# SCH___2021-12-05.net
KiCad netlist of a schematic drawn in EasyEDA
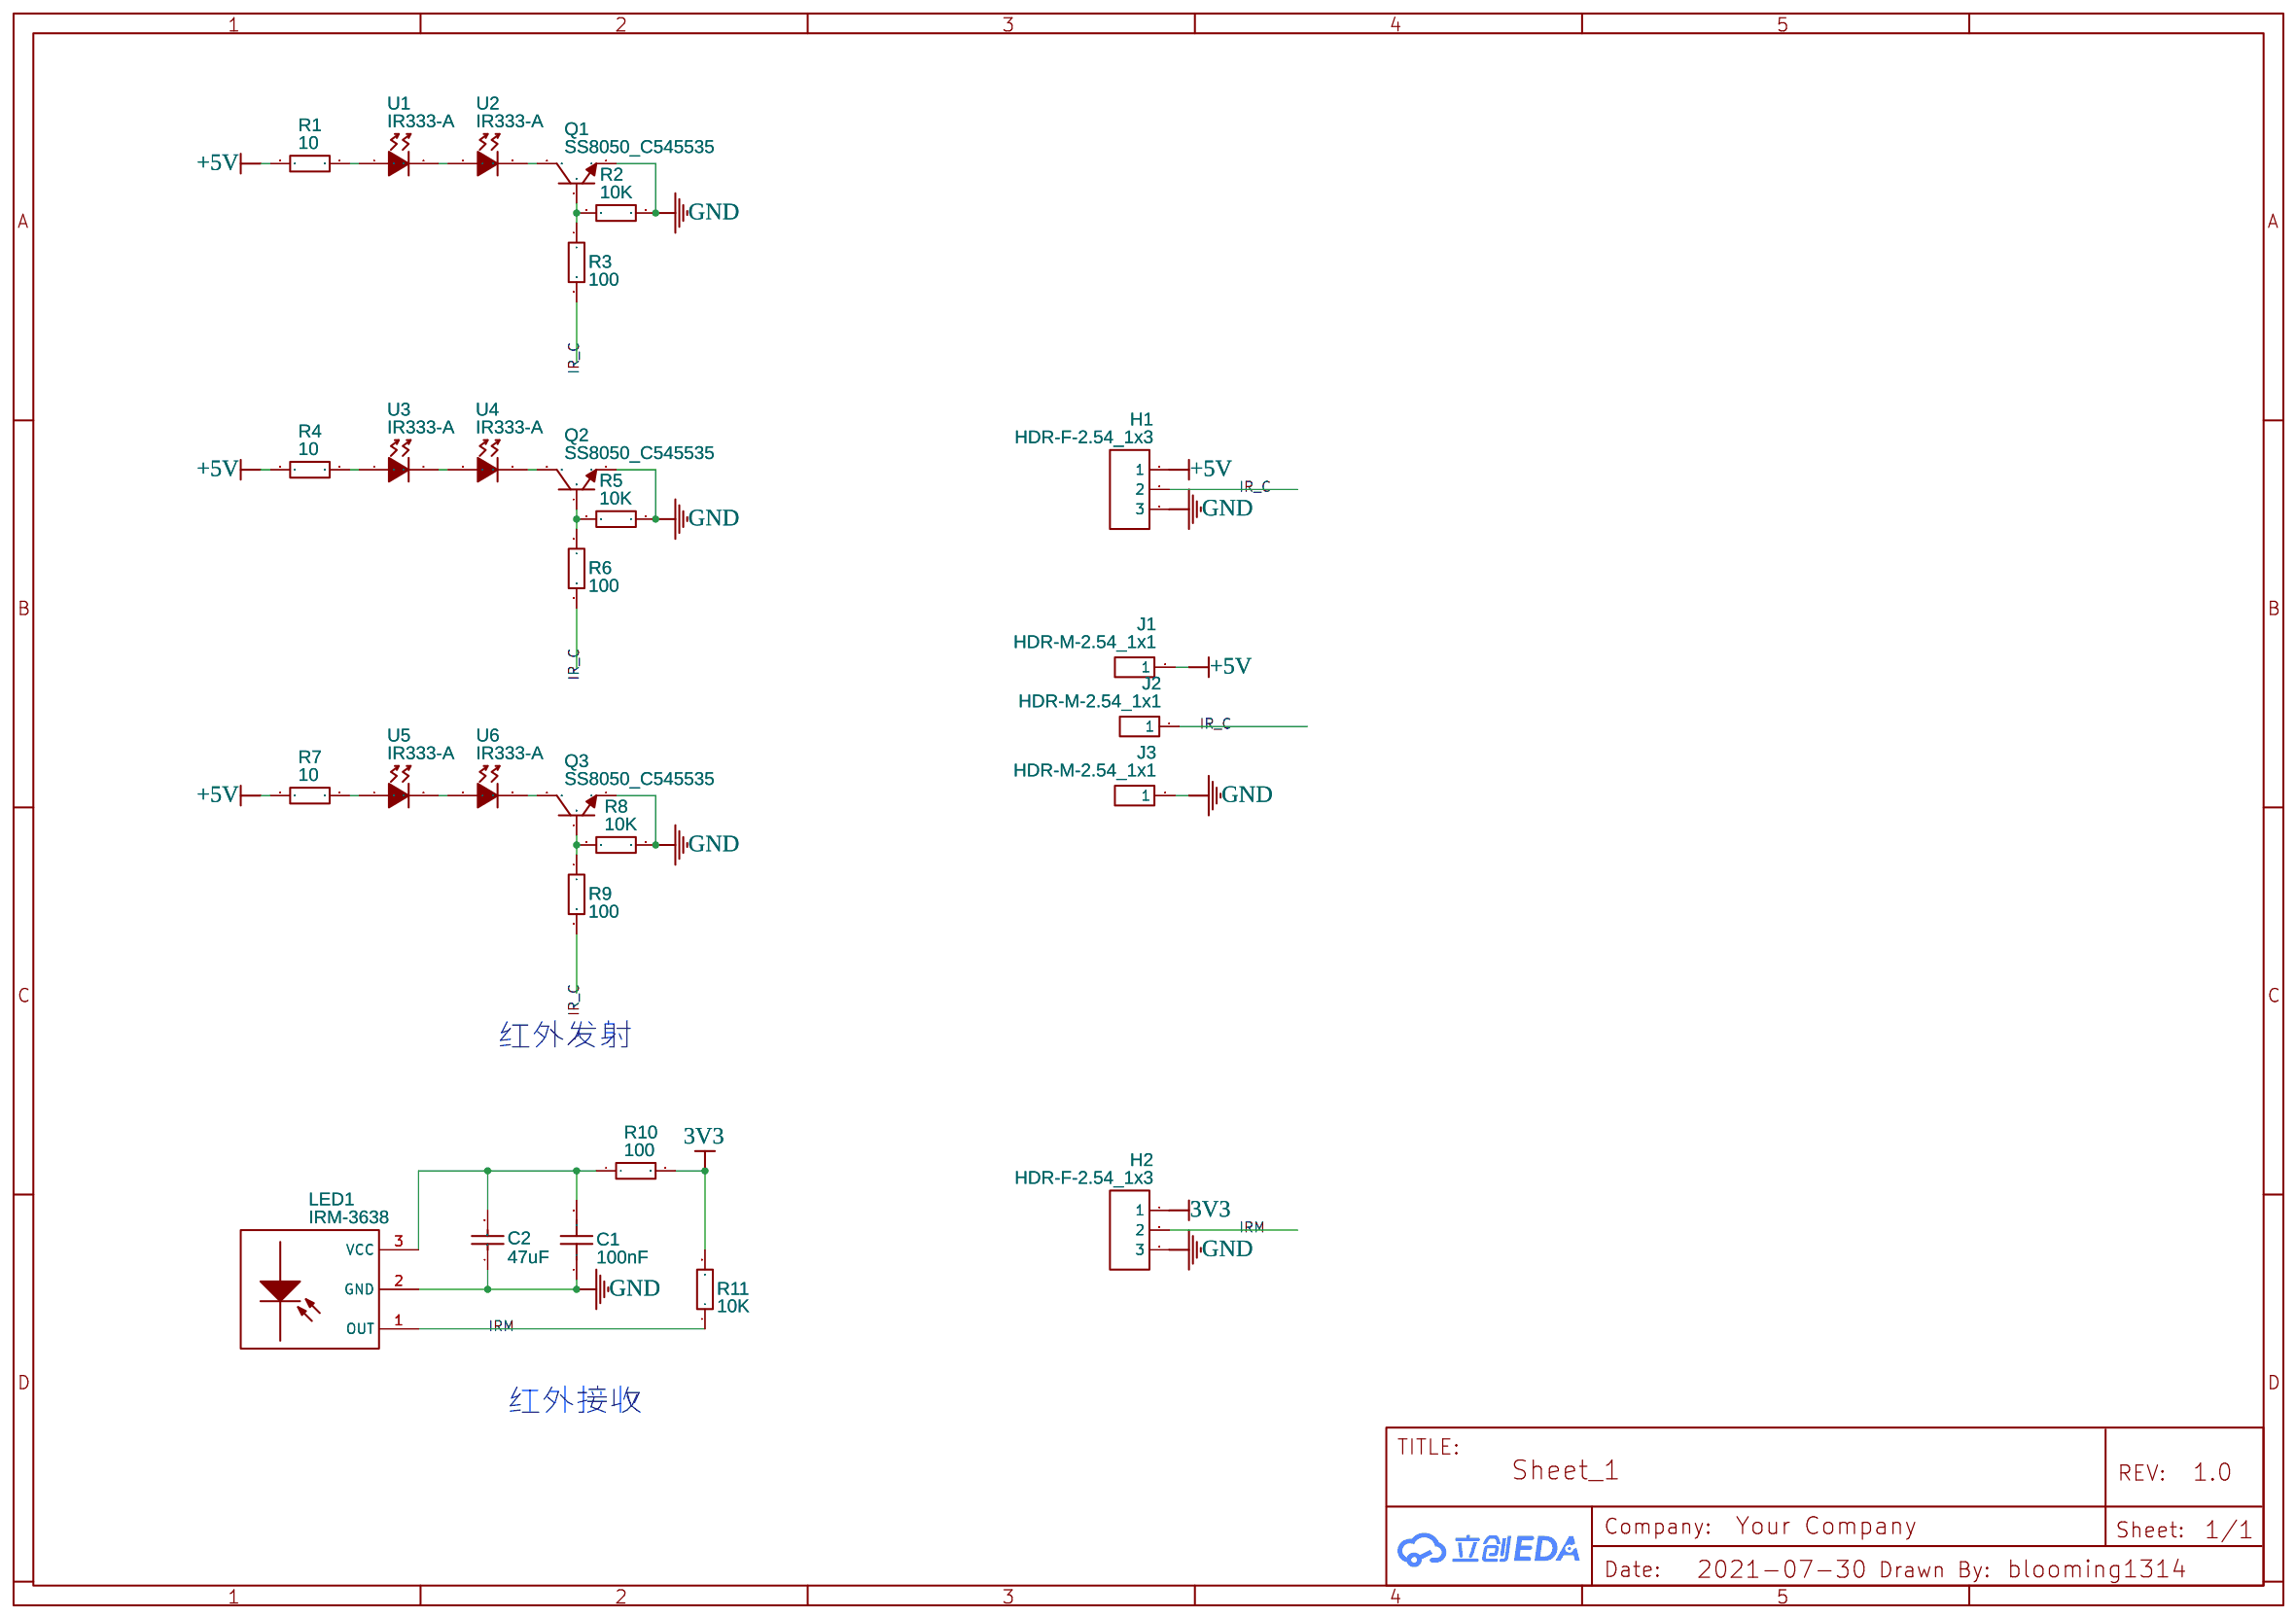
[diagram p0: schematic sheet]

(export (version "E")
  (design (tool "Eeschema 10.0.6"))
  (components
    (comp (ref "C1")
      (value "100nF")
      (fields
        (field (name "BOM_Manufacturer Part") "CC0603KRX7R7BB104")
        (field (name "BOM_Supplier Part") "C108079")
      )
      (libsource (lib "") (part "CC0603KRX7R7BB104"))
    )
    (comp (ref "C2")
      (value "47uF")
      (fields
        (field (name "BOM_Manufacturer Part") "GRM188R60J476ME15D")
        (field (name "BOM_Supplier Part") "C140782")
      )
      (libsource (lib "") (part "GRM188R60J476ME15D"))
    )
    (comp (ref "H1")
      (value "HDR-F-2.54_1x3")
      (fields (field (name "BOM_Supplier Part") "C146690"))
      (libsource (lib "") (part "HDR-F-2.54_1x3"))
    )
    (comp (ref "H2")
      (value "HDR-F-2.54_1x3")
      (fields (field (name "BOM_Supplier Part") "C146690"))
      (libsource (lib "") (part "HDR-F-2.54_1x3"))
    )
    (comp (ref "J1")
      (value "HDR-M-2.54_1x1")
      (fields (field (name "BOM_Supplier Part") "C81276"))
      (libsource (lib "") (part "HDR-M-2.54_1x1"))
    )
    (comp (ref "J2")
      (value "HDR-M-2.54_1x1")
      (fields (field (name "BOM_Supplier Part") "C81276"))
      (libsource (lib "") (part "HDR-M-2.54_1x1_1"))
    )
    (comp (ref "J3")
      (value "HDR-M-2.54_1x1")
      (fields (field (name "BOM_Supplier Part") "C81276"))
      (libsource (lib "") (part "HDR-M-2.54_1x1"))
    )
    (comp (ref "LED1")
      (value "IRM-3638")
      (fields (field (name "BOM_Supplier Part") "C131209"))
      (libsource (lib "") (part "IRM-3638"))
    )
    (comp (ref "Q1")
      (value "SS8050_C545535")
      (fields (field (name "BOM_Manufacturer Part") "SS8050") (field (name "BOM_Supplier Part") "C545535"))
      (libsource (lib "") (part "SS8050_C545535"))
    )
    (comp (ref "Q2")
      (value "SS8050_C545535")
      (fields (field (name "BOM_Manufacturer Part") "SS8050") (field (name "BOM_Supplier Part") "C545535"))
      (libsource (lib "") (part "SS8050_C545535"))
    )
    (comp (ref "Q3")
      (value "SS8050_C545535")
      (fields (field (name "BOM_Manufacturer Part") "SS8050") (field (name "BOM_Supplier Part") "C545535"))
      (libsource (lib "") (part "SS8050_C545535"))
    )
    (comp (ref "R1")
      (value "10")
      (fields
        (field (name "BOM_Manufacturer Part") "AECR0603F10R0K9")
        (field (name "BOM_Supplier Part") "C328336")
      )
      (libsource (lib "") (part "AECR0603F10R0K9"))
    )
    (comp (ref "R2")
      (value "10K")
      (fields
        (field (name "BOM_Manufacturer Part") "0603WAF1002T5E")
        (field (name "BOM_Supplier Part") "C25804")
      )
      (libsource (lib "") (part "0603WAF1002T5E"))
    )
    (comp (ref "R3")
      (value "100")
      (fields
        (field (name "BOM_Manufacturer Part") "0603WAJ0101T5E")
        (field (name "BOM_Supplier Part") "C25201")
      )
      (libsource (lib "") (part "0603WAJ0101T5E"))
    )
    (comp (ref "R4")
      (value "10")
      (fields
        (field (name "BOM_Manufacturer Part") "AECR0603F10R0K9")
        (field (name "BOM_Supplier Part") "C328336")
      )
      (libsource (lib "") (part "AECR0603F10R0K9"))
    )
    (comp (ref "R5")
      (value "10K")
      (fields
        (field (name "BOM_Manufacturer Part") "0603WAF1002T5E")
        (field (name "BOM_Supplier Part") "C25804")
      )
      (libsource (lib "") (part "0603WAF1002T5E"))
    )
    (comp (ref "R6")
      (value "100")
      (fields
        (field (name "BOM_Manufacturer Part") "0603WAJ0101T5E")
        (field (name "BOM_Supplier Part") "C25201")
      )
      (libsource (lib "") (part "0603WAJ0101T5E"))
    )
    (comp (ref "R7")
      (value "10")
      (fields
        (field (name "BOM_Manufacturer Part") "AECR0603F10R0K9")
        (field (name "BOM_Supplier Part") "C328336")
      )
      (libsource (lib "") (part "AECR0603F10R0K9"))
    )
    (comp (ref "R8")
      (value "10K")
      (fields
        (field (name "BOM_Manufacturer Part") "0603WAF1002T5E")
        (field (name "BOM_Supplier Part") "C25804")
      )
      (libsource (lib "") (part "0603WAF1002T5E"))
    )
    (comp (ref "R9")
      (value "100")
      (fields
        (field (name "BOM_Manufacturer Part") "0603WAJ0101T5E")
        (field (name "BOM_Supplier Part") "C25201")
      )
      (libsource (lib "") (part "0603WAJ0101T5E"))
    )
    (comp (ref "R10")
      (value "100")
      (fields
        (field (name "BOM_Manufacturer Part") "0603WAJ0101T5E")
        (field (name "BOM_Supplier Part") "C25201")
      )
      (libsource (lib "") (part "0603WAJ0101T5E_1"))
    )
    (comp (ref "R11")
      (value "10K")
      (fields
        (field (name "BOM_Manufacturer Part") "0603WAF1002T5E")
        (field (name "BOM_Supplier Part") "C25804")
      )
      (libsource (lib "") (part "0603WAF1002T5E_1"))
    )
    (comp (ref "U1")
      (value "IR333-A")
      (fields (field (name "BOM_Supplier Part") "C95407"))
      (libsource (lib "") (part "IR333-A"))
    )
    (comp (ref "U2")
      (value "IR333-A")
      (fields (field (name "BOM_Supplier Part") "C95407"))
      (libsource (lib "") (part "IR333-A"))
    )
    (comp (ref "U3")
      (value "IR333-A")
      (fields (field (name "BOM_Supplier Part") "C95407"))
      (libsource (lib "") (part "IR333-A"))
    )
    (comp (ref "U4")
      (value "IR333-A")
      (fields (field (name "BOM_Supplier Part") "C95407"))
      (libsource (lib "") (part "IR333-A"))
    )
    (comp (ref "U5")
      (value "IR333-A")
      (fields (field (name "BOM_Supplier Part") "C95407"))
      (libsource (lib "") (part "IR333-A"))
    )
    (comp (ref "U6")
      (value "IR333-A")
      (fields (field (name "BOM_Supplier Part") "C95407"))
      (libsource (lib "") (part "IR333-A"))
    )
  )
  (nets
    (net (code "1") (name "+5V") (class "Default")
      (node (ref "H1") (pin "1") (pinfunction "1_1") (pintype "input"))
      (node (ref "J1") (pin "1") (pinfunction "1_1") (pintype "input"))
      (node (ref "R1") (pin "2") (pinfunction "2_2") (pintype "unspecified"))
      (node (ref "R4") (pin "2") (pinfunction "2_2") (pintype "unspecified"))
      (node (ref "R7") (pin "2") (pinfunction "2_2") (pintype "unspecified"))
    )
    (net (code "2") (name "/IRM") (class "Default")
      (node (ref "H2") (pin "2") (pinfunction "2_2") (pintype "input"))
      (node (ref "LED1") (pin "1") (pinfunction "OUT_1") (pintype "input"))
      (node (ref "R11") (pin "1") (pinfunction "1_1") (pintype "input"))
    )
    (net (code "3") (name "/IR_C") (class "Default")
      (node (ref "H1") (pin "2") (pinfunction "2_2") (pintype "input"))
      (node (ref "J2") (pin "1") (pinfunction "1_1") (pintype "input"))
      (node (ref "R3") (pin "2") (pinfunction "2_2") (pintype "input"))
      (node (ref "R6") (pin "2") (pinfunction "2_2") (pintype "input"))
      (node (ref "R9") (pin "2") (pinfunction "2_2") (pintype "input"))
    )
    (net (code "4") (name "3V3") (class "Default")
      (node (ref "H2") (pin "1") (pinfunction "1_1") (pintype "input"))
      (node (ref "R10") (pin "2") (pinfunction "2_2") (pintype "input"))
      (node (ref "R11") (pin "2") (pinfunction "2_2") (pintype "input"))
    )
    (net (code "5") (name "GND") (class "Default")
      (node (ref "C1") (pin "1") (pinfunction "1_1") (pintype "unspecified"))
      (node (ref "C2") (pin "1") (pinfunction "1_1") (pintype "input"))
      (node (ref "H1") (pin "3") (pinfunction "3_3") (pintype "input"))
      (node (ref "H2") (pin "3") (pinfunction "3_3") (pintype "input"))
      (node (ref "J3") (pin "1") (pinfunction "1_1") (pintype "input"))
      (node (ref "LED1") (pin "2") (pinfunction "GND_2") (pintype "input"))
      (node (ref "Q1") (pin "2") (pinfunction "E_2") (pintype "input"))
      (node (ref "Q2") (pin "2") (pinfunction "E_2") (pintype "input"))
      (node (ref "Q3") (pin "2") (pinfunction "E_2") (pintype "input"))
      (node (ref "R2") (pin "1") (pinfunction "1_1") (pintype "input"))
      (node (ref "R5") (pin "1") (pinfunction "1_1") (pintype "input"))
      (node (ref "R8") (pin "1") (pinfunction "1_1") (pintype "input"))
    )
    (net (code "6") (name "Net-(LED1-VCC)") (class "Default")
      (node (ref "C1") (pin "2") (pinfunction "2_2") (pintype "unspecified"))
      (node (ref "C2") (pin "2") (pinfunction "2_2") (pintype "input"))
      (node (ref "LED1") (pin "3") (pinfunction "VCC_3") (pintype "input"))
      (node (ref "R10") (pin "1") (pinfunction "1_1") (pintype "input"))
    )
    (net (code "7") (name "Net-(Q1-B)") (class "Default")
      (node (ref "Q1") (pin "1") (pinfunction "B_1") (pintype "input"))
      (node (ref "R2") (pin "2") (pinfunction "2_2") (pintype "input"))
      (node (ref "R3") (pin "1") (pinfunction "1_1") (pintype "input"))
    )
    (net (code "8") (name "Net-(Q1-C)") (class "Default")
      (node (ref "Q1") (pin "3") (pinfunction "C_3") (pintype "input"))
      (node (ref "U2") (pin "2") (pinfunction "C_2") (pintype "input"))
    )
    (net (code "9") (name "Net-(Q2-B)") (class "Default")
      (node (ref "Q2") (pin "1") (pinfunction "B_1") (pintype "input"))
      (node (ref "R5") (pin "2") (pinfunction "2_2") (pintype "input"))
      (node (ref "R6") (pin "1") (pinfunction "1_1") (pintype "input"))
    )
    (net (code "10") (name "Net-(Q2-C)") (class "Default")
      (node (ref "Q2") (pin "3") (pinfunction "C_3") (pintype "input"))
      (node (ref "U4") (pin "2") (pinfunction "C_2") (pintype "input"))
    )
    (net (code "11") (name "Net-(Q3-B)") (class "Default")
      (node (ref "Q3") (pin "1") (pinfunction "B_1") (pintype "input"))
      (node (ref "R8") (pin "2") (pinfunction "2_2") (pintype "input"))
      (node (ref "R9") (pin "1") (pinfunction "1_1") (pintype "input"))
    )
    (net (code "12") (name "Net-(Q3-C)") (class "Default")
      (node (ref "Q3") (pin "3") (pinfunction "C_3") (pintype "input"))
      (node (ref "U6") (pin "2") (pinfunction "C_2") (pintype "input"))
    )
    (net (code "13") (name "Net-(U1-A)") (class "Default")
      (node (ref "R1") (pin "1") (pinfunction "1_1") (pintype "unspecified"))
      (node (ref "U1") (pin "1") (pinfunction "A_1") (pintype "input"))
    )
    (net (code "14") (name "Net-(U1-C)") (class "Default")
      (node (ref "U1") (pin "2") (pinfunction "C_2") (pintype "input"))
      (node (ref "U2") (pin "1") (pinfunction "A_1") (pintype "input"))
    )
    (net (code "15") (name "Net-(U3-A)") (class "Default")
      (node (ref "R4") (pin "1") (pinfunction "1_1") (pintype "unspecified"))
      (node (ref "U3") (pin "1") (pinfunction "A_1") (pintype "input"))
    )
    (net (code "16") (name "Net-(U3-C)") (class "Default")
      (node (ref "U3") (pin "2") (pinfunction "C_2") (pintype "input"))
      (node (ref "U4") (pin "1") (pinfunction "A_1") (pintype "input"))
    )
    (net (code "17") (name "Net-(U5-A)") (class "Default")
      (node (ref "R7") (pin "1") (pinfunction "1_1") (pintype "unspecified"))
      (node (ref "U5") (pin "1") (pinfunction "A_1") (pintype "input"))
    )
    (net (code "18") (name "Net-(U5-C)") (class "Default")
      (node (ref "U5") (pin "2") (pinfunction "C_2") (pintype "input"))
      (node (ref "U6") (pin "1") (pinfunction "A_1") (pintype "input"))
    )
  )
)
